# HP85disk.net
KiCad netlist of a schematic drawn in EAGLE
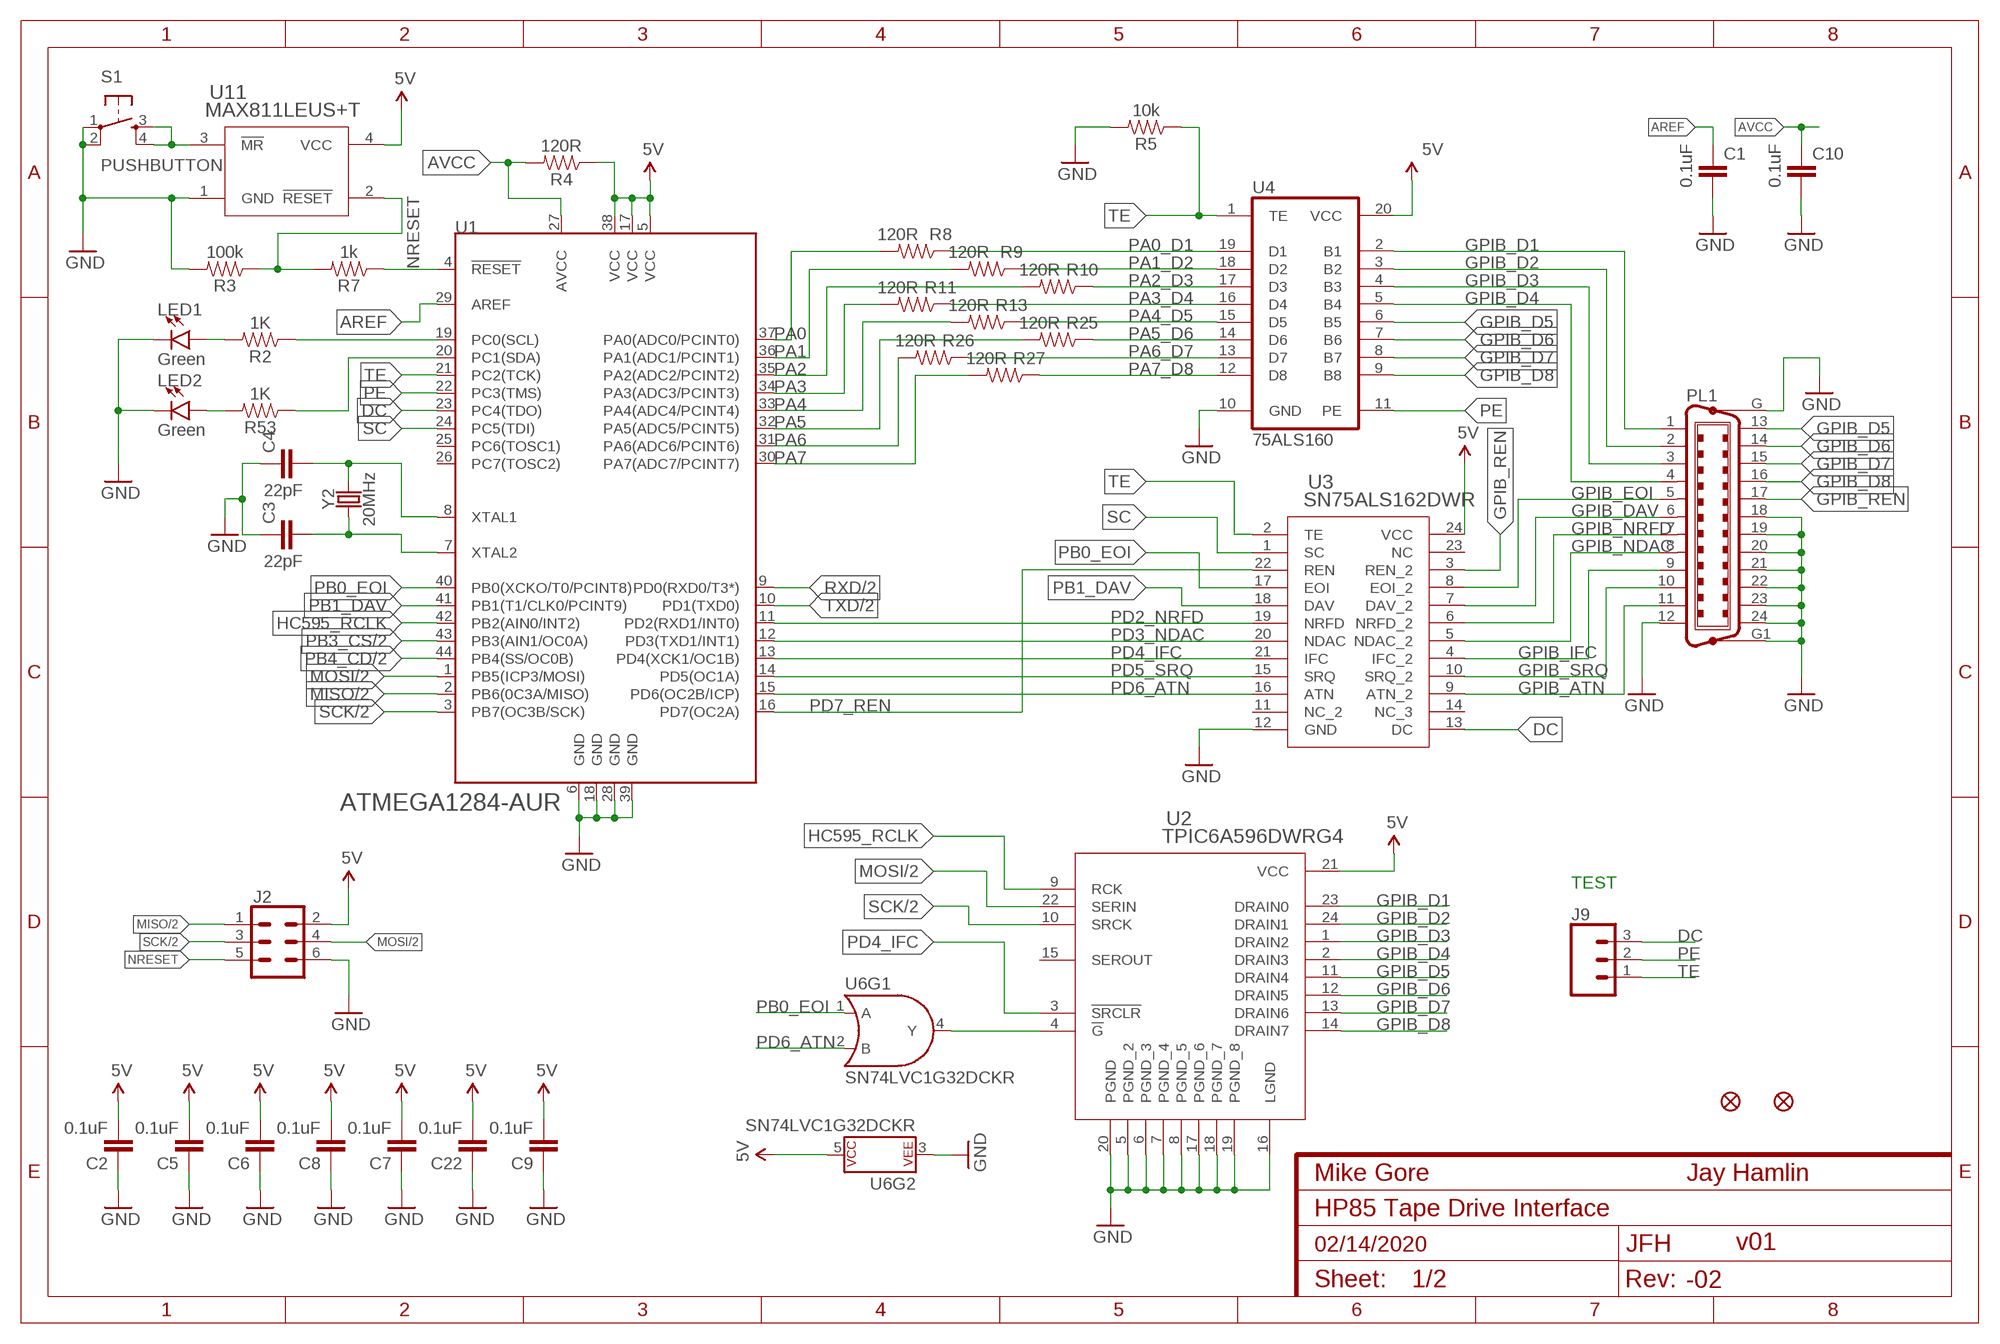
[diagram p0: schematic, sheet 1]
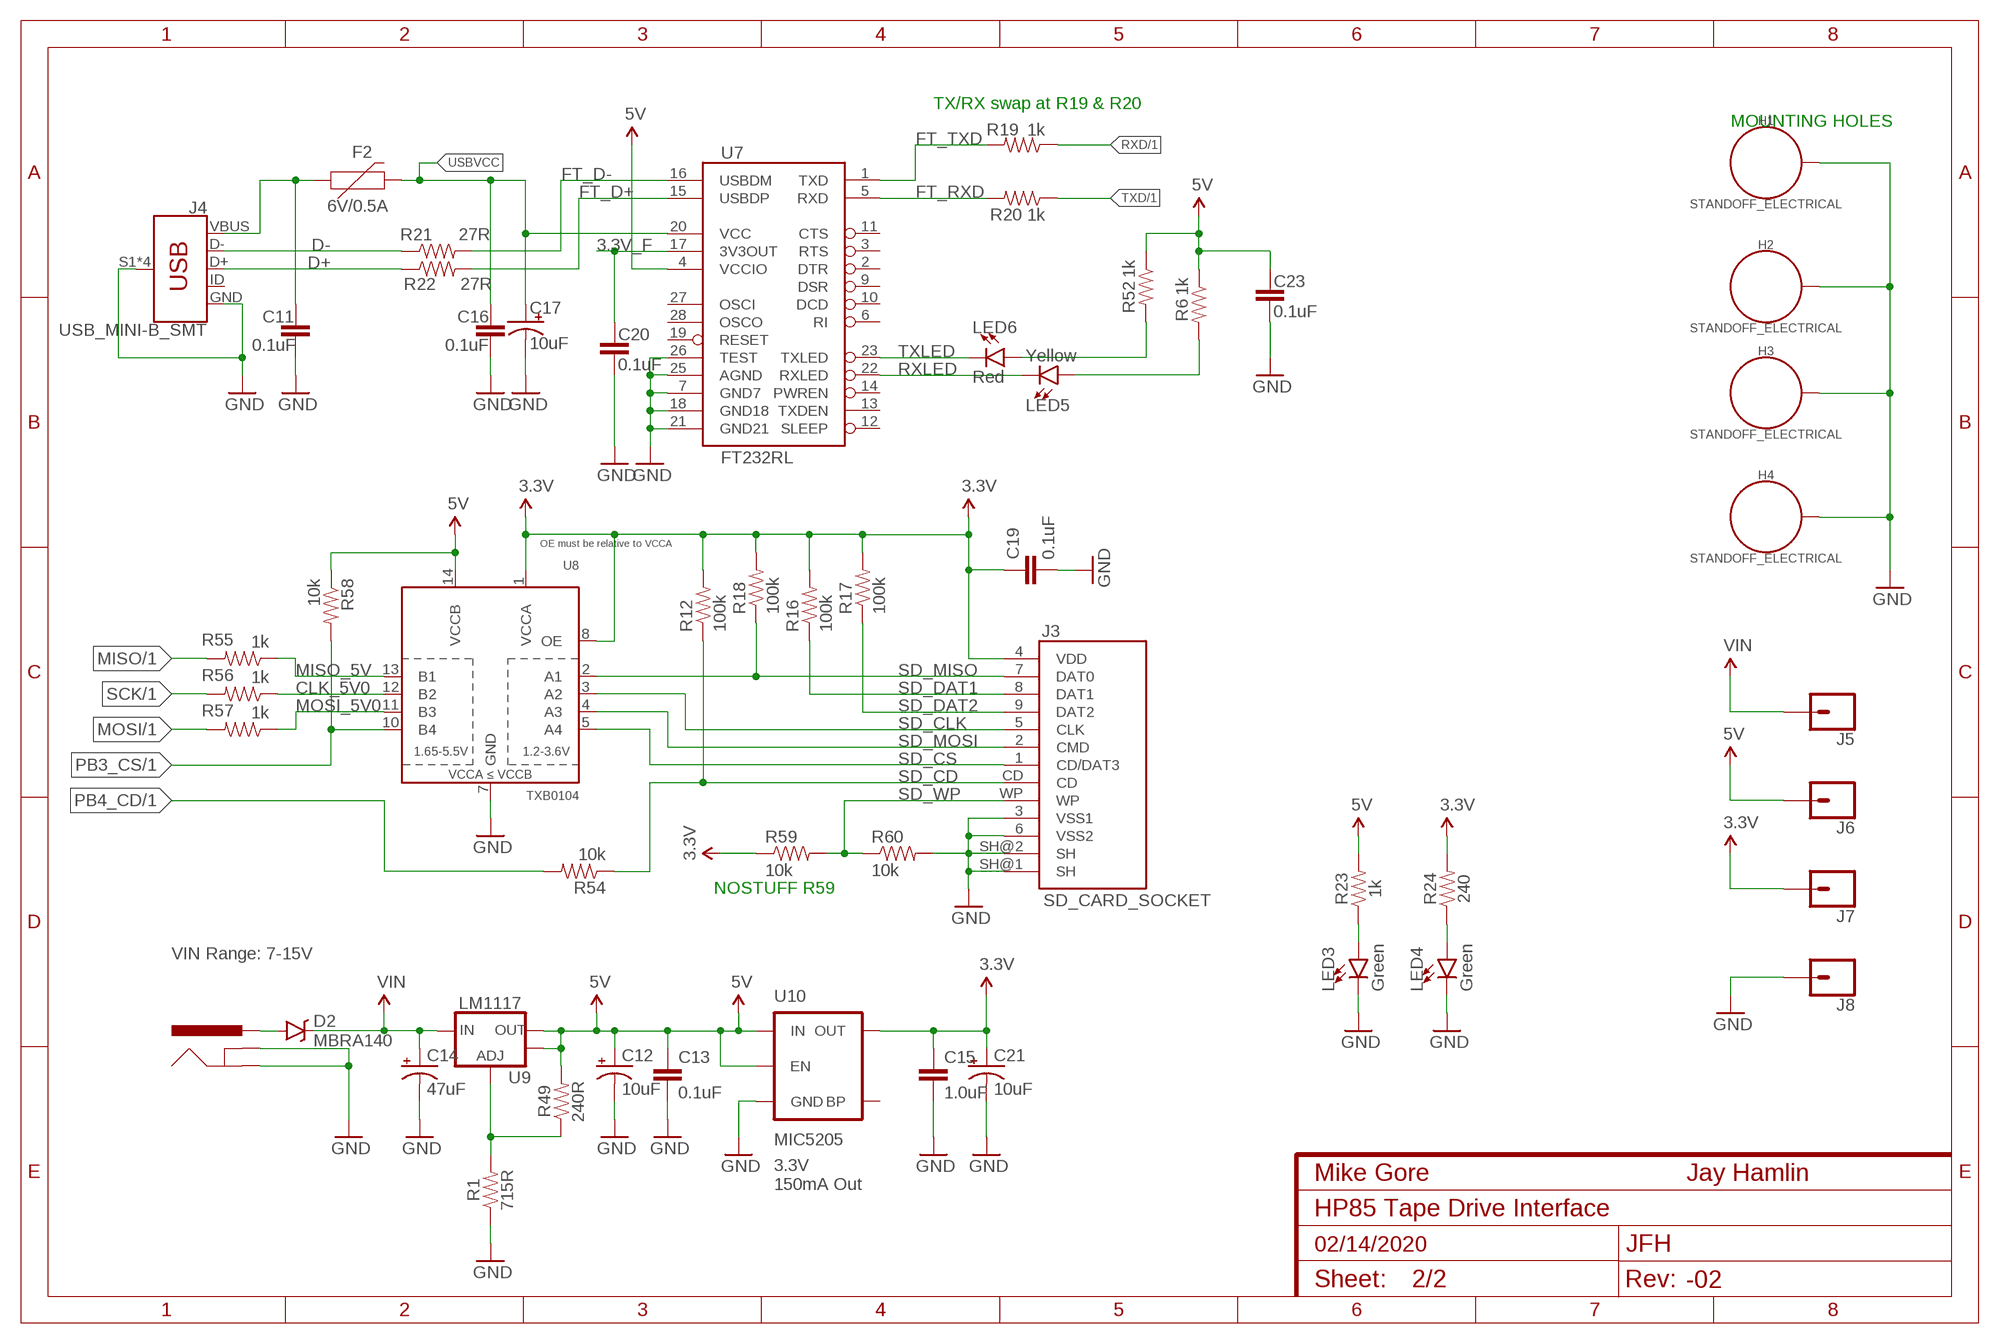
[diagram p1: schematic, sheet 2]

(export (version "E")
  (design (tool "Eeschema 10.0.6"))
  (components
    (comp (ref "C11")
      (value "0.1uF")
      (footprint "eagle-import:0603")
      (libsource (lib "eagle-import") (part "0.1UF-0603-25V-(+80/-20%)"))
    )
    (comp (ref "C12")
      (value "10uF")
      (footprint "eagle-import:EIA3216")
      (libsource (lib "eagle-import") (part "10UF-POLAR-EIA3216-16V-10%(TANT)"))
    )
    (comp (ref "C13")
      (value "0.1uF")
      (footprint "eagle-import:0603")
      (libsource (lib "eagle-import") (part "0.1UF-0603-25V-(+80/-20%)"))
    )
    (comp (ref "C14")
      (value "47uF")
      (footprint "eagle-import:PANASONIC_D")
      (libsource (lib "eagle-import") (part "47UF-POLAR-PANASONIC_D-35V-20%"))
    )
    (comp (ref "C15")
      (value "1.0uF")
      (footprint "eagle-import:0603")
      (libsource (lib "eagle-import") (part "1.0UF-0603-16V-10%"))
    )
    (comp (ref "C16")
      (value "0.1uF")
      (footprint "eagle-import:0603")
      (libsource (lib "eagle-import") (part "0.1UF-0603-25V-(+80/-20%)"))
    )
    (comp (ref "C17")
      (value "10uF")
      (footprint "eagle-import:EIA3216")
      (libsource (lib "eagle-import") (part "10UF-POLAR-EIA3216-16V-10%(TANT)"))
    )
    (comp (ref "C19")
      (value "0.1uF")
      (footprint "eagle-import:0603")
      (libsource (lib "eagle-import") (part "0.1UF-0603-25V-(+80/-20%)"))
    )
    (comp (ref "C20")
      (value "0.1uF")
      (footprint "eagle-import:0603")
      (libsource (lib "eagle-import") (part "0.1UF-0603-25V-(+80/-20%)"))
    )
    (comp (ref "C21")
      (value "10uF")
      (footprint "eagle-import:EIA3216")
      (libsource (lib "eagle-import") (part "10UF-POLAR-EIA3216-16V-10%(TANT)"))
    )
    (comp (ref "C23")
      (value "0.1uF")
      (footprint "eagle-import:0603")
      (libsource (lib "eagle-import") (part "0.1UF-0603-25V-(+80/-20%)"))
    )
    (comp (ref "D2")
      (value "MBRA140")
      (footprint "eagle-import:SMA-DIODE")
      (libsource (lib "eagle-import") (part "MBRA140"))
    )
    (comp (ref "F2")
      (value "6V/0.5A")
      (footprint "eagle-import:1206")
      (libsource (lib "eagle-import") (part "PTC-HALF_AMP"))
    )
    (comp (ref "H1")
      (value "STANDOFF_ELECTRICAL")
      (footprint "eagle-import:STANDOFF-ELECTRICAL")
      (libsource (lib "eagle-import") (part "STANDOFF_ELECTRICAL"))
    )
    (comp (ref "H2")
      (value "STANDOFF_ELECTRICAL")
      (footprint "eagle-import:STANDOFF-ELECTRICAL")
      (libsource (lib "eagle-import") (part "STANDOFF_ELECTRICAL"))
    )
    (comp (ref "H3")
      (value "STANDOFF_ELECTRICAL")
      (footprint "eagle-import:STANDOFF-ELECTRICAL")
      (libsource (lib "eagle-import") (part "STANDOFF_ELECTRICAL"))
    )
    (comp (ref "H4")
      (value "STANDOFF_ELECTRICAL")
      (footprint "eagle-import:STANDOFF-ELECTRICAL")
      (libsource (lib "eagle-import") (part "STANDOFF_ELECTRICAL"))
    )
    (comp (ref "J1")
      (value "POWER_JACKSUPER_BOMB_DIGITY")
      (footprint "eagle-import:POWER_JACK_SMD_OVERPASTE_SUPER_BOMB_DIGITY")
      (libsource (lib "eagle-import") (part "POWER_JACKSUPER_BOMB_DIGITY"))
    )
    (comp (ref "J3")
      (value "SD_CARD_SOCKET")
      (footprint "eagle-import:SD_1_1")
      (libsource (lib "eagle-import") (part "SD_CARD_SOCKET"))
    )
    (comp (ref "J4")
      (value "USB_MINI-B_SMT")
      (footprint "eagle-import:USB-MINIB")
      (libsource (lib "eagle-import") (part "USB_MINI-B_SMT"))
    )
    (comp (ref "J5")
      (value "CONN_01")
      (footprint "eagle-import:1X01")
      (libsource (lib "eagle-import") (part "CONN_01"))
    )
    (comp (ref "J6")
      (value "CONN_01")
      (footprint "eagle-import:1X01")
      (libsource (lib "eagle-import") (part "CONN_01"))
    )
    (comp (ref "J7")
      (value "CONN_01")
      (footprint "eagle-import:1X01")
      (libsource (lib "eagle-import") (part "CONN_01"))
    )
    (comp (ref "J8")
      (value "CONN_01")
      (footprint "eagle-import:1X01")
      (libsource (lib "eagle-import") (part "CONN_01"))
    )
    (comp (ref "LED3")
      (value "Green")
      (footprint "eagle-import:LED-1206")
      (libsource (lib "eagle-import") (part "LED1206"))
    )
    (comp (ref "LED4")
      (value "Green")
      (footprint "eagle-import:LED-1206")
      (libsource (lib "eagle-import") (part "LED1206"))
    )
    (comp (ref "LED5")
      (value "Yellow")
      (footprint "eagle-import:LED-1206")
      (libsource (lib "eagle-import") (part "LED1206"))
    )
    (comp (ref "LED6")
      (value "Red")
      (footprint "eagle-import:LED-1206")
      (libsource (lib "eagle-import") (part "LED1206"))
    )
    (comp (ref "R1")
      (value "715R")
      (footprint "eagle-import:0603")
      (libsource (lib "eagle-import") (part "715OHM-0603-1/10W-1%"))
    )
    (comp (ref "R6")
      (value "1k")
      (footprint "eagle-import:0603")
      (libsource (lib "eagle-import") (part "1KOHM-0603-1/10W-1%"))
    )
    (comp (ref "R12")
      (value "100k")
      (footprint "eagle-import:0603-RES")
      (libsource (lib "eagle-import") (part "100KOHM-1/10W-1%(0603)"))
    )
    (comp (ref "R16")
      (value "100k")
      (footprint "eagle-import:0603-RES")
      (libsource (lib "eagle-import") (part "100KOHM-1/10W-1%(0603)"))
    )
    (comp (ref "R17")
      (value "100k")
      (footprint "eagle-import:0603-RES")
      (libsource (lib "eagle-import") (part "100KOHM-1/10W-1%(0603)"))
    )
    (comp (ref "R18")
      (value "100k")
      (footprint "eagle-import:0603-RES")
      (libsource (lib "eagle-import") (part "100KOHM-1/10W-1%(0603)"))
    )
    (comp (ref "R19")
      (value "1k")
      (footprint "eagle-import:0603")
      (libsource (lib "eagle-import") (part "1KOHM-0603-1/10W-1%"))
    )
    (comp (ref "R20")
      (value "1k")
      (footprint "eagle-import:0603")
      (libsource (lib "eagle-import") (part "1KOHM-0603-1/10W-1%"))
    )
    (comp (ref "R21")
      (value "27R")
      (footprint "eagle-import:0603")
      (libsource (lib "eagle-import") (part "27OHM-0603-1/10W-1%"))
    )
    (comp (ref "R22")
      (value "27R")
      (footprint "eagle-import:0603")
      (libsource (lib "eagle-import") (part "27OHM-0603-1/10W-1%"))
    )
    (comp (ref "R23")
      (value "1k")
      (footprint "eagle-import:0603")
      (libsource (lib "eagle-import") (part "4.7KOHM-0603-1/10W-1%"))
    )
    (comp (ref "R24")
      (value "240")
      (footprint "eagle-import:0603")
      (libsource (lib "eagle-import") (part "4.7KOHM-0603-1/10W-1%"))
    )
    (comp (ref "R49")
      (value "240R")
      (footprint "eagle-import:0603")
      (libsource (lib "eagle-import") (part "240OHM-0603-1/10W-1%"))
    )
    (comp (ref "R52")
      (value "1k")
      (footprint "eagle-import:0603")
      (libsource (lib "eagle-import") (part "1KOHM-0603-1/10W-1%"))
    )
    (comp (ref "R54")
      (value "10k")
      (footprint "eagle-import:0603-RES")
      (libsource (lib "eagle-import") (part "100KOHM-1/10W-1%(0603)"))
    )
    (comp (ref "R55")
      (value "1k")
      (footprint "eagle-import:0603-RES")
      (libsource (lib "eagle-import") (part "100KOHM-1/10W-1%(0603)"))
    )
    (comp (ref "R56")
      (value "1k")
      (footprint "eagle-import:0603-RES")
      (libsource (lib "eagle-import") (part "100KOHM-1/10W-1%(0603)"))
    )
    (comp (ref "R57")
      (value "1k")
      (footprint "eagle-import:0603-RES")
      (libsource (lib "eagle-import") (part "100KOHM-1/10W-1%(0603)"))
    )
    (comp (ref "R58")
      (value "10k")
      (footprint "eagle-import:0603-RES")
      (libsource (lib "eagle-import") (part "100KOHM-1/10W-1%(0603)"))
    )
    (comp (ref "R59")
      (value "10k")
      (footprint "eagle-import:0603-RES")
      (libsource (lib "eagle-import") (part "100KOHM-1/10W-1%(0603)"))
    )
    (comp (ref "R60")
      (value "10k")
      (footprint "eagle-import:0603-RES")
      (libsource (lib "eagle-import") (part "100KOHM-1/10W-1%(0603)"))
    )
    (comp (ref "U7")
      (value "FT232RL")
      (footprint "eagle-import:SSOP28DB")
      (libsource (lib "eagle-import") (part "FT232RLSSOP"))
    )
    (comp (ref "U8")
      (value "TXB0104")
      (footprint "eagle-import:SO14")
      (libsource (lib "eagle-import") (part "TXB0104PWRSOIC14"))
    )
    (comp (ref "U9")
      (value "LM1117")
      (footprint "eagle-import:SOT223-ALT1")
      (libsource (lib "eagle-import") (part "V_REG_LM1117ALT1"))
    )
    (comp (ref "U10")
      (value "MIC5205")
      (footprint "eagle-import:SOT23-5")
      (libsource (lib "eagle-import") (part "MIC52053.3V"))
    )
    (comp (ref "C1")
      (value "0.1uF")
      (footprint "eagle-import:0603")
      (libsource (lib "eagle-import") (part "0.1UF-0603-25V-(+80/-20%)"))
    )
    (comp (ref "C2")
      (value "0.1uF")
      (footprint "eagle-import:0603")
      (fields (field (name "SPICEPREFIX") "C"))
      (libsource (lib "eagle-import") (part "0.1UF-0603-25V-(+80/-20%)"))
    )
    (comp (ref "C3")
      (value "22pF")
      (footprint "eagle-import:0603")
      (libsource (lib "eagle-import") (part "0.1UF-0603-25V-(+80/-20%)"))
    )
    (comp (ref "C4")
      (value "22pF")
      (footprint "eagle-import:0603")
      (libsource (lib "eagle-import") (part "0.1UF-0603-25V-(+80/-20%)"))
    )
    (comp (ref "C5")
      (value "0.1uF")
      (footprint "eagle-import:0603")
      (fields (field (name "SPICEPREFIX") "C"))
      (libsource (lib "eagle-import") (part "0.1UF-0603-25V-(+80/-20%)"))
    )
    (comp (ref "C6")
      (value "0.1uF")
      (footprint "eagle-import:0603")
      (fields (field (name "SPICEPREFIX") "C"))
      (libsource (lib "eagle-import") (part "0.1UF-0603-25V-(+80/-20%)"))
    )
    (comp (ref "C7")
      (value "0.1uF")
      (footprint "eagle-import:0603")
      (fields (field (name "SPICEPREFIX") "C"))
      (libsource (lib "eagle-import") (part "0.1UF-0603-25V-(+80/-20%)"))
    )
    (comp (ref "C8")
      (value "0.1uF")
      (footprint "eagle-import:0603")
      (fields (field (name "SPICEPREFIX") "C"))
      (libsource (lib "eagle-import") (part "0.1UF-0603-25V-(+80/-20%)"))
    )
    (comp (ref "C9")
      (value "0.1uF")
      (footprint "eagle-import:0603")
      (libsource (lib "eagle-import") (part "0.1UF-0603-25V-(+80/-20%)"))
    )
    (comp (ref "C10")
      (value "0.1uF")
      (footprint "eagle-import:0603")
      (libsource (lib "eagle-import") (part "0.1UF-0603-25V-(+80/-20%)"))
    )
    (comp (ref "C22")
      (value "0.1uF")
      (footprint "eagle-import:0603")
      (libsource (lib "eagle-import") (part "0.1UF-0603-25V-(+80/-20%)"))
    )
    (comp (ref "J2")
      (value "CONN_03X2_BIGPADSFEMALE_SMD")
      (footprint "eagle-import:2X3_SMD")
      (libsource (lib "eagle-import") (part "CONN_03X2_BIGPADSFEMALE_SMD"))
    )
    (comp (ref "J9")
      (value "CONN_03")
      (footprint "eagle-import:1X03")
      (libsource (lib "eagle-import") (part "CONN_03"))
    )
    (comp (ref "JP8")
      (value "FIDUCIAL1X2")
      (footprint "eagle-import:FIDUCIAL-1X2")
      (libsource (lib "eagle-import") (part "FIDUCIAL1X2"))
    )
    (comp (ref "JP9")
      (value "FIDUCIAL1X2")
      (footprint "eagle-import:FIDUCIAL-1X2")
      (libsource (lib "eagle-import") (part "FIDUCIAL1X2"))
    )
    (comp (ref "LED1")
      (value "Green")
      (footprint "eagle-import:LED-1206")
      (libsource (lib "eagle-import") (part "LED1206"))
    )
    (comp (ref "LED2")
      (value "Green")
      (footprint "eagle-import:LED-1206")
      (libsource (lib "eagle-import") (part "LED1206"))
    )
    (comp (ref "PL1")
      (value "C24HP")
      (footprint "eagle-import:24HP")
      (libsource (lib "eagle-import") (part "C24HP"))
    )
    (comp (ref "R2")
      (value "1K")
      (footprint "eagle-import:0603")
      (libsource (lib "eagle-import") (part "4.7KOHM-0603-1/10W-1%"))
    )
    (comp (ref "R3")
      (value "100k")
      (footprint "eagle-import:0603")
      (libsource (lib "eagle-import") (part "10KOHM-0603-1/10W-1%"))
    )
    (comp (ref "R4")
      (value "120R")
      (footprint "eagle-import:0603")
      (libsource (lib "eagle-import") (part "10KOHM-0603-1/10W-1%"))
    )
    (comp (ref "R5")
      (value "10k")
      (footprint "eagle-import:0603")
      (libsource (lib "eagle-import") (part "10KOHM-0603-1/10W-1%"))
    )
    (comp (ref "R7")
      (value "1k")
      (footprint "eagle-import:0603")
      (libsource (lib "eagle-import") (part "10KOHM-0603-1/10W-1%"))
    )
    (comp (ref "R8")
      (value "120R")
      (footprint "eagle-import:0603")
      (libsource (lib "eagle-import") (part "10KOHM-0603-1/10W-1%"))
    )
    (comp (ref "R9")
      (value "120R")
      (footprint "eagle-import:0603")
      (libsource (lib "eagle-import") (part "10KOHM-0603-1/10W-1%"))
    )
    (comp (ref "R10")
      (value "120R")
      (footprint "eagle-import:0603")
      (libsource (lib "eagle-import") (part "10KOHM-0603-1/10W-1%"))
    )
    (comp (ref "R11")
      (value "120R")
      (footprint "eagle-import:0603")
      (libsource (lib "eagle-import") (part "10KOHM-0603-1/10W-1%"))
    )
    (comp (ref "R13")
      (value "120R")
      (footprint "eagle-import:0603")
      (libsource (lib "eagle-import") (part "10KOHM-0603-1/10W-1%"))
    )
    (comp (ref "R25")
      (value "120R")
      (footprint "eagle-import:0603")
      (libsource (lib "eagle-import") (part "10KOHM-0603-1/10W-1%"))
    )
    (comp (ref "R26")
      (value "120R")
      (footprint "eagle-import:0603")
      (libsource (lib "eagle-import") (part "10KOHM-0603-1/10W-1%"))
    )
    (comp (ref "R27")
      (value "120R")
      (footprint "eagle-import:0603")
      (libsource (lib "eagle-import") (part "10KOHM-0603-1/10W-1%"))
    )
    (comp (ref "R53")
      (value "1K")
      (footprint "eagle-import:0603")
      (libsource (lib "eagle-import") (part "4.7KOHM-0603-1/10W-1%"))
    )
    (comp (ref "S1")
      (value "PUSHBUTTON")
      (footprint "eagle-import:TACTILE-SWITCH-SMD")
      (libsource (lib "eagle-import") (part "SWITCH_SPST_4_PINSQUARE"))
    )
    (comp (ref "U1")
      (value "ATMEGA1284-AUR")
      (footprint "eagle-import:TQFP44")
      (libsource (lib "eagle-import") (part "ATMEGA1284AUTQFP-44"))
    )
    (comp (ref "U2")
      (value "TPIC6A596DWRG4")
      (footprint "eagle-import:DW24")
      (fields (field (name "MANUFACTURER") "Texas Instruments"))
      (libsource (lib "eagle-import") (part "TPIC6A596DWRG4"))
    )
    (comp (ref "U3")
      (value "SN75ALS162DWR")
      (footprint "eagle-import:DW24")
      (fields (field (name "MANUFACTURER") "Texas Instruments"))
      (libsource (lib "eagle-import") (part "SN75ALS162DWR"))
    )
    (comp (ref "U4")
      (value "75ALS160")
      (footprint "eagle-import:SO20L")
      (libsource (lib "eagle-import") (part "75160SO"))
    )
    (comp (ref "U6")
      (value "SN74LVC1G32DCKR")
      (footprint "eagle-import:SOT23-5")
      (libsource (lib "eagle-import") (part "7432DBVLVC"))
    )
    (comp (ref "U11")
      (value "MAX811LEUS+T")
      (footprint "eagle-import:21-0052F")
      (fields
        (field (name "MANUFACTURER_PART_NUMBER") "MAX811TEUS+T")
        (field (name "COPYRIGHT") "Copyright (C) 2018 Accelerated Designs. All rights reserved")
      )
      (libsource (lib "eagle-import") (part "MAX811TEUS+T"))
    )
    (comp (ref "Y2")
      (value "20MHz")
      (footprint "eagle-import:CRYSTAL-SMD-5X3.2-4PAD")
      (libsource (lib "eagle-import") (part "CRYSTAL-16MHZSMD-5X3.2"))
    )
  )
  (nets
    (net (code "1") (name "3.3V") (class "Default")
      (node (ref "C15") (pin "1") (pinfunction "1_1") (pintype "passive"))
      (node (ref "C19") (pin "1") (pinfunction "1_1") (pintype "passive"))
      (node (ref "C21") (pin "+") (pinfunction "+_+") (pintype "passive"))
      (node (ref "J3") (pin "4") (pinfunction "VDD_4") (pintype "power_in"))
      (node (ref "J7") (pin "1") (pinfunction "1_1") (pintype "passive"))
      (node (ref "R12") (pin "2") (pinfunction "2_2") (pintype "passive"))
      (node (ref "R16") (pin "2") (pinfunction "2_2") (pintype "passive"))
      (node (ref "R17") (pin "2") (pinfunction "2_2") (pintype "passive"))
      (node (ref "R18") (pin "2") (pinfunction "2_2") (pintype "passive"))
      (node (ref "R24") (pin "2") (pinfunction "2_2") (pintype "passive"))
      (node (ref "R59") (pin "1") (pinfunction "1_1") (pintype "passive"))
      (node (ref "U10") (pin "5") (pinfunction "OUT_5") (pintype "passive"))
      (node (ref "U8") (pin "1") (pinfunction "VCCA_1") (pintype "bidirectional"))
      (node (ref "U8") (pin "8") (pinfunction "OE_8") (pintype "bidirectional"))
    )
    (net (code "2") (name "3.3V_F") (class "Default")
      (node (ref "C20") (pin "1") (pinfunction "1_1") (pintype "passive"))
      (node (ref "U7") (pin "17") (pinfunction "3V3OUT_17") (pintype "output"))
    )
    (net (code "3") (name "5V") (class "Default")
      (node (ref "C12") (pin "+") (pinfunction "+_+") (pintype "passive"))
      (node (ref "C13") (pin "1") (pinfunction "1_1") (pintype "passive"))
      (node (ref "C2") (pin "2") (pinfunction "2_2") (pintype "passive"))
      (node (ref "C22") (pin "2") (pinfunction "2_2") (pintype "passive"))
      (node (ref "C23") (pin "1") (pinfunction "1_1") (pintype "passive"))
      (node (ref "C5") (pin "2") (pinfunction "2_2") (pintype "passive"))
      (node (ref "C6") (pin "2") (pinfunction "2_2") (pintype "passive"))
      (node (ref "C7") (pin "2") (pinfunction "2_2") (pintype "passive"))
      (node (ref "C8") (pin "2") (pinfunction "2_2") (pintype "passive"))
      (node (ref "C9") (pin "2") (pinfunction "2_2") (pintype "passive"))
      (node (ref "J2") (pin "2") (pinfunction "2_2") (pintype "bidirectional"))
      (node (ref "J6") (pin "1") (pinfunction "1_1") (pintype "passive"))
      (node (ref "R23") (pin "2") (pinfunction "2_2") (pintype "passive"))
      (node (ref "R4") (pin "1") (pinfunction "1_1") (pintype "passive"))
      (node (ref "R49") (pin "2") (pinfunction "2_2") (pintype "passive"))
      (node (ref "R52") (pin "1") (pinfunction "1_1") (pintype "passive"))
      (node (ref "R58") (pin "1") (pinfunction "1_1") (pintype "passive"))
      (node (ref "R6") (pin "1") (pinfunction "1_1") (pintype "passive"))
      (node (ref "U1") (pin "17") (pinfunction "VCC_17") (pintype "bidirectional"))
      (node (ref "U1") (pin "38") (pinfunction "VCC_38") (pintype "bidirectional"))
      (node (ref "U1") (pin "5") (pinfunction "VCC_5") (pintype "bidirectional"))
      (node (ref "U10") (pin "1") (pinfunction "IN_1") (pintype "input"))
      (node (ref "U10") (pin "3") (pinfunction "EN_3") (pintype "input"))
      (node (ref "U11") (pin "4") (pinfunction "VCC_4") (pintype "power_in"))
      (node (ref "U2") (pin "21") (pinfunction "VCC_21") (pintype "power_in"))
      (node (ref "U3") (pin "24") (pinfunction "VCC_24") (pintype "power_in"))
      (node (ref "U4") (pin "20") (pinfunction "VCC_20") (pintype "bidirectional"))
      (node (ref "U6") (pin "5") (pinfunction "P$V+_5") (pintype "bidirectional"))
      (node (ref "U7") (pin "4") (pinfunction "VCCIO_4") (pintype "power_in"))
      (node (ref "U8") (pin "14") (pinfunction "VCCB_14") (pintype "bidirectional"))
      (node (ref "U9") (pin "2") (pinfunction "OUT_2") (pintype "output"))
      (node (ref "U9") (pin "4") (pinfunction "OUT_4") (pintype "output"))
    )
    (net (code "4") (name "AREF") (class "Default")
      (node (ref "C1") (pin "1") (pinfunction "1_1") (pintype "passive"))
      (node (ref "U1") (pin "29") (pinfunction "AREF_29") (pintype "bidirectional"))
    )
    (net (code "5") (name "AVCC") (class "Default")
      (node (ref "C10") (pin "1") (pinfunction "1_1") (pintype "passive"))
      (node (ref "R4") (pin "2") (pinfunction "2_2") (pintype "passive"))
      (node (ref "U1") (pin "27") (pinfunction "AVCC_27") (pintype "bidirectional"))
    )
    (net (code "6") (name "CLK_5V0") (class "Default")
      (node (ref "R56") (pin "1") (pinfunction "1_1") (pintype "passive"))
      (node (ref "U8") (pin "12") (pinfunction "B2_12") (pintype "bidirectional"))
    )
    (net (code "7") (name "D+") (class "Default")
      (node (ref "J4") (pin "D+") (pinfunction "D+_D+") (pintype "bidirectional"))
      (node (ref "R22") (pin "1") (pinfunction "1_1") (pintype "passive"))
    )
    (net (code "8") (name "D-") (class "Default")
      (node (ref "J4") (pin "D-") (pinfunction "D-_D-") (pintype "bidirectional"))
      (node (ref "R21") (pin "1") (pinfunction "1_1") (pintype "passive"))
    )
    (net (code "9") (name "DC") (class "Default")
      (node (ref "J9") (pin "3") (pinfunction "3_3") (pintype "passive"))
      (node (ref "U1") (pin "23") (pinfunction "PC4(TDO)_23") (pintype "bidirectional"))
      (node (ref "U3") (pin "13") (pinfunction "DC_13") (pintype "input"))
    )
    (net (code "10") (name "FT_D+") (class "Default")
      (node (ref "R22") (pin "2") (pinfunction "2_2") (pintype "passive"))
      (node (ref "U7") (pin "15") (pinfunction "USBDP_15") (pintype "bidirectional"))
    )
    (net (code "11") (name "FT_D-") (class "Default")
      (node (ref "R21") (pin "2") (pinfunction "2_2") (pintype "passive"))
      (node (ref "U7") (pin "16") (pinfunction "USBDM_16") (pintype "bidirectional"))
    )
    (net (code "12") (name "FT_RXD") (class "Default")
      (node (ref "R20") (pin "2") (pinfunction "2_2") (pintype "passive"))
      (node (ref "U7") (pin "5") (pinfunction "RXD_5") (pintype "input"))
    )
    (net (code "13") (name "FT_TXD") (class "Default")
      (node (ref "R19") (pin "2") (pinfunction "2_2") (pintype "passive"))
      (node (ref "U7") (pin "1") (pinfunction "TXD_1") (pintype "output"))
    )
    (net (code "14") (name "GND") (class "Default")
      (node (ref "C1") (pin "2") (pinfunction "2_2") (pintype "passive"))
      (node (ref "C10") (pin "2") (pinfunction "2_2") (pintype "passive"))
      (node (ref "C11") (pin "2") (pinfunction "2_2") (pintype "passive"))
      (node (ref "C12") (pin "-") (pinfunction "-_-") (pintype "passive"))
      (node (ref "C13") (pin "2") (pinfunction "2_2") (pintype "passive"))
      (node (ref "C14") (pin "-") (pinfunction "-_-") (pintype "passive"))
      (node (ref "C15") (pin "2") (pinfunction "2_2") (pintype "passive"))
      (node (ref "C16") (pin "2") (pinfunction "2_2") (pintype "passive"))
      (node (ref "C17") (pin "-") (pinfunction "-_-") (pintype "passive"))
      (node (ref "C19") (pin "2") (pinfunction "2_2") (pintype "passive"))
      (node (ref "C2") (pin "1") (pinfunction "1_1") (pintype "passive"))
      (node (ref "C20") (pin "2") (pinfunction "2_2") (pintype "passive"))
      (node (ref "C21") (pin "-") (pinfunction "-_-") (pintype "passive"))
      (node (ref "C22") (pin "1") (pinfunction "1_1") (pintype "passive"))
      (node (ref "C23") (pin "2") (pinfunction "2_2") (pintype "passive"))
      (node (ref "C3") (pin "1") (pinfunction "1_1") (pintype "passive"))
      (node (ref "C4") (pin "1") (pinfunction "1_1") (pintype "passive"))
      (node (ref "C5") (pin "1") (pinfunction "1_1") (pintype "passive"))
      (node (ref "C6") (pin "1") (pinfunction "1_1") (pintype "passive"))
      (node (ref "C7") (pin "1") (pinfunction "1_1") (pintype "passive"))
      (node (ref "C8") (pin "1") (pinfunction "1_1") (pintype "passive"))
      (node (ref "C9") (pin "1") (pinfunction "1_1") (pintype "passive"))
      (node (ref "H1") (pin "P1") (pinfunction "P$1_P1") (pintype "bidirectional"))
      (node (ref "H2") (pin "P1") (pinfunction "P$1_P1") (pintype "bidirectional"))
      (node (ref "H3") (pin "P1") (pinfunction "P$1_P1") (pintype "bidirectional"))
      (node (ref "H4") (pin "P1") (pinfunction "P$1_P1") (pintype "bidirectional"))
      (node (ref "J1") (pin "GND") (pinfunction "GNDBREAK_GND") (pintype "bidirectional"))
      (node (ref "J1") (pin "P$4") (pinfunction "GND_P$4") (pintype "bidirectional"))
      (node (ref "J2") (pin "6") (pinfunction "6_6") (pintype "bidirectional"))
      (node (ref "J3") (pin "3") (pinfunction "VSS1_3") (pintype "power_in"))
      (node (ref "J3") (pin "6") (pinfunction "VSS2_6") (pintype "power_in"))
      (node (ref "J3") (pin "SH@1") (pinfunction "SH_SH@1") (pintype "bidirectional"))
      (node (ref "J3") (pin "SH@2") (pinfunction "SH_SH@2") (pintype "bidirectional"))
      (node (ref "J4") (pin "GND") (pinfunction "GND_GND") (pintype "power_in"))
      (node (ref "J4") (pin "S1") (pinfunction "SHIELD_S1") (pintype "bidirectional"))
      (node (ref "J4") (pin "S2") (pinfunction "SHIELD_S2") (pintype "bidirectional"))
      (node (ref "J4") (pin "S3") (pinfunction "SHIELD_S3") (pintype "bidirectional"))
      (node (ref "J4") (pin "S4") (pinfunction "SHIELD_S4") (pintype "bidirectional"))
      (node (ref "J8") (pin "1") (pinfunction "1_1") (pintype "passive"))
      (node (ref "LED1") (pin "C") (pinfunction "C_C") (pintype "passive"))
      (node (ref "LED2") (pin "C") (pinfunction "C_C") (pintype "passive"))
      (node (ref "LED3") (pin "C") (pinfunction "C_C") (pintype "passive"))
      (node (ref "LED4") (pin "C") (pinfunction "C_C") (pintype "passive"))
      (node (ref "PL1") (pin "12") (pinfunction "12_12") (pintype "passive"))
      (node (ref "PL1") (pin "18") (pinfunction "18_18") (pintype "passive"))
      (node (ref "PL1") (pin "19") (pinfunction "19_19") (pintype "passive"))
      (node (ref "PL1") (pin "20") (pinfunction "20_20") (pintype "passive"))
      (node (ref "PL1") (pin "21") (pinfunction "21_21") (pintype "passive"))
      (node (ref "PL1") (pin "22") (pinfunction "22_22") (pintype "passive"))
      (node (ref "PL1") (pin "23") (pinfunction "23_23") (pintype "passive"))
      (node (ref "PL1") (pin "24") (pinfunction "24_24") (pintype "passive"))
      (node (ref "PL1") (pin "G") (pinfunction "G_G") (pintype "passive"))
      (node (ref "PL1") (pin "G1") (pinfunction "G1_G1") (pintype "passive"))
      (node (ref "R1") (pin "1") (pinfunction "1_1") (pintype "passive"))
      (node (ref "R3") (pin "2") (pinfunction "2_2") (pintype "passive"))
      (node (ref "R5") (pin "2") (pinfunction "2_2") (pintype "passive"))
      (node (ref "R60") (pin "2") (pinfunction "2_2") (pintype "passive"))
      (node (ref "S1") (pin "1") (pinfunction "1_1") (pintype "passive"))
      (node (ref "S1") (pin "2") (pinfunction "2_2") (pintype "passive"))
      (node (ref "U1") (pin "18") (pinfunction "GND_18") (pintype "bidirectional"))
      (node (ref "U1") (pin "28") (pinfunction "GND_28") (pintype "bidirectional"))
      (node (ref "U1") (pin "39") (pinfunction "GND_39") (pintype "bidirectional"))
      (node (ref "U1") (pin "6") (pinfunction "GND_6") (pintype "bidirectional"))
      (node (ref "U10") (pin "2") (pinfunction "GND_2") (pintype "input"))
      (node (ref "U11") (pin "1") (pinfunction "GND_1") (pintype "power_in"))
      (node (ref "U2") (pin "16") (pinfunction "LGND_16") (pintype "power_in"))
      (node (ref "U2") (pin "17") (pinfunction "PGND_6_17") (pintype "power_in"))
      (node (ref "U2") (pin "18") (pinfunction "PGND_7_18") (pintype "power_in"))
      (node (ref "U2") (pin "19") (pinfunction "PGND_8_19") (pintype "power_in"))
      (node (ref "U2") (pin "20") (pinfunction "PGND_20") (pintype "power_in"))
      (node (ref "U2") (pin "5") (pinfunction "PGND_2_5") (pintype "power_in"))
      (node (ref "U2") (pin "6") (pinfunction "PGND_3_6") (pintype "power_in"))
      (node (ref "U2") (pin "7") (pinfunction "PGND_4_7") (pintype "power_in"))
      (node (ref "U2") (pin "8") (pinfunction "PGND_5_8") (pintype "power_in"))
      (node (ref "U3") (pin "12") (pinfunction "GND_12") (pintype "power_in"))
      (node (ref "U4") (pin "10") (pinfunction "GND_10") (pintype "bidirectional"))
      (node (ref "U6") (pin "3") (pinfunction "P$V-_3") (pintype "bidirectional"))
      (node (ref "U7") (pin "18") (pinfunction "GND18_18") (pintype "power_in"))
      (node (ref "U7") (pin "21") (pinfunction "GND21_21") (pintype "power_in"))
      (node (ref "U7") (pin "25") (pinfunction "AGND_25") (pintype "power_in"))
      (node (ref "U7") (pin "26") (pinfunction "TEST_26") (pintype "input"))
      (node (ref "U7") (pin "7") (pinfunction "GND7_7") (pintype "power_in"))
      (node (ref "U8") (pin "7") (pinfunction "GND_7") (pintype "bidirectional"))
    )
    (net (code "15") (name "GPIB_ATN") (class "Default")
      (node (ref "PL1") (pin "11") (pinfunction "11_11") (pintype "passive"))
      (node (ref "U3") (pin "9") (pinfunction "ATN_2_9") (pintype "bidirectional"))
    )
    (net (code "16") (name "GPIB_D1") (class "Default")
      (node (ref "PL1") (pin "1") (pinfunction "1_1") (pintype "passive"))
      (node (ref "U2") (pin "23") (pinfunction "DRAIN0_23") (pintype "output"))
      (node (ref "U4") (pin "2") (pinfunction "B1_2") (pintype "bidirectional"))
    )
    (net (code "17") (name "GPIB_D2") (class "Default")
      (node (ref "PL1") (pin "2") (pinfunction "2_2") (pintype "passive"))
      (node (ref "U2") (pin "24") (pinfunction "DRAIN1_24") (pintype "output"))
      (node (ref "U4") (pin "3") (pinfunction "B2_3") (pintype "bidirectional"))
    )
    (net (code "18") (name "GPIB_D3") (class "Default")
      (node (ref "PL1") (pin "3") (pinfunction "3_3") (pintype "passive"))
      (node (ref "U2") (pin "1") (pinfunction "DRAIN2_1") (pintype "output"))
      (node (ref "U4") (pin "4") (pinfunction "B3_4") (pintype "bidirectional"))
    )
    (net (code "19") (name "GPIB_D4") (class "Default")
      (node (ref "PL1") (pin "4") (pinfunction "4_4") (pintype "passive"))
      (node (ref "U2") (pin "2") (pinfunction "DRAIN3_2") (pintype "output"))
      (node (ref "U4") (pin "5") (pinfunction "B4_5") (pintype "bidirectional"))
    )
    (net (code "20") (name "GPIB_D5") (class "Default")
      (node (ref "PL1") (pin "13") (pinfunction "13_13") (pintype "passive"))
      (node (ref "U2") (pin "11") (pinfunction "DRAIN4_11") (pintype "output"))
      (node (ref "U4") (pin "6") (pinfunction "B5_6") (pintype "bidirectional"))
    )
    (net (code "21") (name "GPIB_D6") (class "Default")
      (node (ref "PL1") (pin "14") (pinfunction "14_14") (pintype "passive"))
      (node (ref "U2") (pin "12") (pinfunction "DRAIN5_12") (pintype "output"))
      (node (ref "U4") (pin "7") (pinfunction "B6_7") (pintype "bidirectional"))
    )
    (net (code "22") (name "GPIB_D7") (class "Default")
      (node (ref "PL1") (pin "15") (pinfunction "15_15") (pintype "passive"))
      (node (ref "U2") (pin "13") (pinfunction "DRAIN6_13") (pintype "output"))
      (node (ref "U4") (pin "8") (pinfunction "B7_8") (pintype "bidirectional"))
    )
    (net (code "23") (name "GPIB_D8") (class "Default")
      (node (ref "PL1") (pin "16") (pinfunction "16_16") (pintype "passive"))
      (node (ref "U2") (pin "14") (pinfunction "DRAIN7_14") (pintype "output"))
      (node (ref "U4") (pin "9") (pinfunction "B8_9") (pintype "bidirectional"))
    )
    (net (code "24") (name "GPIB_DAV") (class "Default")
      (node (ref "PL1") (pin "6") (pinfunction "6_6") (pintype "passive"))
      (node (ref "U3") (pin "7") (pinfunction "DAV_2_7") (pintype "bidirectional"))
    )
    (net (code "25") (name "GPIB_EOI") (class "Default")
      (node (ref "PL1") (pin "5") (pinfunction "5_5") (pintype "passive"))
      (node (ref "U3") (pin "8") (pinfunction "EOI_2_8") (pintype "bidirectional"))
    )
    (net (code "26") (name "GPIB_IFC") (class "Default")
      (node (ref "PL1") (pin "9") (pinfunction "9_9") (pintype "passive"))
      (node (ref "U3") (pin "4") (pinfunction "IFC_2_4") (pintype "bidirectional"))
    )
    (net (code "27") (name "GPIB_NDAC") (class "Default")
      (node (ref "PL1") (pin "8") (pinfunction "8_8") (pintype "passive"))
      (node (ref "U3") (pin "5") (pinfunction "NDAC_2_5") (pintype "bidirectional"))
    )
    (net (code "28") (name "GPIB_NRFD") (class "Default")
      (node (ref "PL1") (pin "7") (pinfunction "7_7") (pintype "passive"))
      (node (ref "U3") (pin "6") (pinfunction "NRFD_2_6") (pintype "bidirectional"))
    )
    (net (code "29") (name "GPIB_REN") (class "Default")
      (node (ref "PL1") (pin "17") (pinfunction "17_17") (pintype "passive"))
      (node (ref "U3") (pin "3") (pinfunction "REN_2_3") (pintype "bidirectional"))
    )
    (net (code "30") (name "GPIB_SRQ") (class "Default")
      (node (ref "PL1") (pin "10") (pinfunction "10_10") (pintype "passive"))
      (node (ref "U3") (pin "10") (pinfunction "SRQ_2_10") (pintype "bidirectional"))
    )
    (net (code "31") (name "HC595_RCLK") (class "Default")
      (node (ref "U1") (pin "42") (pinfunction "PB2(AIN0/INT2)_42") (pintype "bidirectional"))
      (node (ref "U2") (pin "9") (pinfunction "RCK_9") (pintype "input"))
    )
    (net (code "32") (name "MISO") (class "Default")
      (node (ref "J2") (pin "1") (pinfunction "1_1") (pintype "bidirectional"))
      (node (ref "R55") (pin "2") (pinfunction "2_2") (pintype "passive"))
      (node (ref "U1") (pin "2") (pinfunction "PB6(0C3A/MISO)_2") (pintype "bidirectional"))
    )
    (net (code "33") (name "MISO_5V") (class "Default")
      (node (ref "R55") (pin "1") (pinfunction "1_1") (pintype "passive"))
      (node (ref "U8") (pin "13") (pinfunction "B1_13") (pintype "bidirectional"))
    )
    (net (code "34") (name "MOSI") (class "Default")
      (node (ref "J2") (pin "4") (pinfunction "4_4") (pintype "bidirectional"))
      (node (ref "R57") (pin "2") (pinfunction "2_2") (pintype "passive"))
      (node (ref "U1") (pin "1") (pinfunction "PB5(ICP3/MOSI)_1") (pintype "bidirectional"))
      (node (ref "U2") (pin "22") (pinfunction "SERIN_22") (pintype "input"))
    )
    (net (code "35") (name "MOSI_5V0") (class "Default")
      (node (ref "R57") (pin "1") (pinfunction "1_1") (pintype "passive"))
      (node (ref "U8") (pin "11") (pinfunction "B3_11") (pintype "bidirectional"))
    )
    (net (code "36") (name "NRESET") (class "Default")
      (node (ref "J2") (pin "5") (pinfunction "5_5") (pintype "bidirectional"))
      (node (ref "R7") (pin "1") (pinfunction "1_1") (pintype "passive"))
      (node (ref "U1") (pin "4") (pinfunction "~{RESET}_4") (pintype "bidirectional"))
    )
    (net (code "37") (name "Net-(C11-Pad1)") (class "Default")
      (node (ref "C11") (pin "1") (pinfunction "1_1") (pintype "passive"))
      (node (ref "F2") (pin "1") (pinfunction "1_1") (pintype "bidirectional"))
      (node (ref "J4") (pin "VBUS") (pinfunction "VBUS_VBUS") (pintype "power_in"))
    )
    (net (code "38") (name "Net-(J1-PWR)") (class "Default")
      (node (ref "D2") (pin "A") (pinfunction "A_A") (pintype "passive"))
      (node (ref "J1") (pin "VIN0") (pinfunction "PWR_VIN0") (pintype "bidirectional"))
    )
    (net (code "39") (name "Net-(LED1-PadA)") (class "Default")
      (node (ref "LED1") (pin "A") (pinfunction "A_A") (pintype "passive"))
      (node (ref "R2") (pin "2") (pinfunction "2_2") (pintype "passive"))
    )
    (net (code "40") (name "Net-(LED2-PadA)") (class "Default")
      (node (ref "LED2") (pin "A") (pinfunction "A_A") (pintype "passive"))
      (node (ref "R53") (pin "2") (pinfunction "2_2") (pintype "passive"))
    )
    (net (code "41") (name "Net-(LED3-PadA)") (class "Default")
      (node (ref "LED3") (pin "A") (pinfunction "A_A") (pintype "passive"))
      (node (ref "R23") (pin "1") (pinfunction "1_1") (pintype "passive"))
    )
    (net (code "42") (name "Net-(LED4-PadA)") (class "Default")
      (node (ref "LED4") (pin "A") (pinfunction "A_A") (pintype "passive"))
      (node (ref "R24") (pin "1") (pinfunction "1_1") (pintype "passive"))
    )
    (net (code "43") (name "Net-(LED5-PadA)") (class "Default")
      (node (ref "LED5") (pin "A") (pinfunction "A_A") (pintype "passive"))
      (node (ref "R6") (pin "2") (pinfunction "2_2") (pintype "passive"))
    )
    (net (code "44") (name "Net-(LED6-PadA)") (class "Default")
      (node (ref "LED6") (pin "A") (pinfunction "A_A") (pintype "passive"))
      (node (ref "R52") (pin "2") (pinfunction "2_2") (pintype "passive"))
    )
    (net (code "45") (name "Net-(U1-PC0(SCL))") (class "Default")
      (node (ref "R2") (pin "1") (pinfunction "1_1") (pintype "passive"))
      (node (ref "U1") (pin "19") (pinfunction "PC0(SCL)_19") (pintype "bidirectional"))
    )
    (net (code "46") (name "Net-(U1-PC1(SDA))") (class "Default")
      (node (ref "R53") (pin "1") (pinfunction "1_1") (pintype "passive"))
      (node (ref "U1") (pin "20") (pinfunction "PC1(SDA)_20") (pintype "bidirectional"))
    )
    (net (code "47") (name "Net-(U1-XTAL1)") (class "Default")
      (node (ref "C4") (pin "2") (pinfunction "2_2") (pintype "passive"))
      (node (ref "U1") (pin "8") (pinfunction "XTAL1_8") (pintype "bidirectional"))
      (node (ref "Y2") (pin "3") (pinfunction "2_3") (pintype "passive"))
    )
    (net (code "48") (name "Net-(U1-XTAL2)") (class "Default")
      (node (ref "C3") (pin "2") (pinfunction "2_2") (pintype "passive"))
      (node (ref "U1") (pin "7") (pinfunction "XTAL2_7") (pintype "bidirectional"))
      (node (ref "Y2") (pin "1") (pinfunction "1_1") (pintype "passive"))
    )
    (net (code "49") (name "Net-(U2-~{G})") (class "Default")
      (node (ref "U2") (pin "4") (pinfunction "~{G}_4") (pintype "input"))
      (node (ref "U6") (pin "4") (pinfunction "Y_4") (pintype "bidirectional"))
    )
    (net (code "50") (name "Net-(U9-ADJ)") (class "Default")
      (node (ref "R1") (pin "2") (pinfunction "2_2") (pintype "passive"))
      (node (ref "R49") (pin "1") (pinfunction "1_1") (pintype "passive"))
      (node (ref "U9") (pin "1") (pinfunction "ADJ_1") (pintype "input"))
    )
    (net (code "51") (name "Net-(U11-~{MR})") (class "Default")
      (node (ref "S1") (pin "3") (pinfunction "3_3") (pintype "passive"))
      (node (ref "S1") (pin "4") (pinfunction "4_4") (pintype "passive"))
      (node (ref "U11") (pin "3") (pinfunction "~{MR}_3") (pintype "input"))
    )
    (net (code "52") (name "Net-(U11-~{RESET})") (class "Default")
      (node (ref "R3") (pin "1") (pinfunction "1_1") (pintype "passive"))
      (node (ref "R7") (pin "2") (pinfunction "2_2") (pintype "passive"))
      (node (ref "U11") (pin "2") (pinfunction "~{RESET}_2") (pintype "output"))
    )
    (net (code "53") (name "PA0") (class "Default")
      (node (ref "R8") (pin "2") (pinfunction "2_2") (pintype "passive"))
      (node (ref "U1") (pin "37") (pinfunction "PA0(ADC0/PCINT0)_37") (pintype "bidirectional"))
    )
    (net (code "54") (name "PA0_D1") (class "Default")
      (node (ref "R8") (pin "1") (pinfunction "1_1") (pintype "passive"))
      (node (ref "U4") (pin "19") (pinfunction "D1_19") (pintype "bidirectional"))
    )
    (net (code "55") (name "PA1") (class "Default")
      (node (ref "R9") (pin "2") (pinfunction "2_2") (pintype "passive"))
      (node (ref "U1") (pin "36") (pinfunction "PA1(ADC1/PCINT1)_36") (pintype "bidirectional"))
    )
    (net (code "56") (name "PA1_D2") (class "Default")
      (node (ref "R9") (pin "1") (pinfunction "1_1") (pintype "passive"))
      (node (ref "U4") (pin "18") (pinfunction "D2_18") (pintype "bidirectional"))
    )
    (net (code "57") (name "PA2") (class "Default")
      (node (ref "R10") (pin "2") (pinfunction "2_2") (pintype "passive"))
      (node (ref "U1") (pin "35") (pinfunction "PA2(ADC2/PCINT2)_35") (pintype "bidirectional"))
    )
    (net (code "58") (name "PA2_D3") (class "Default")
      (node (ref "R10") (pin "1") (pinfunction "1_1") (pintype "passive"))
      (node (ref "U4") (pin "17") (pinfunction "D3_17") (pintype "bidirectional"))
    )
    (net (code "59") (name "PA3") (class "Default")
      (node (ref "R11") (pin "2") (pinfunction "2_2") (pintype "passive"))
      (node (ref "U1") (pin "34") (pinfunction "PA3(ADC3/PCINT3)_34") (pintype "bidirectional"))
    )
    (net (code "60") (name "PA3_D4") (class "Default")
      (node (ref "R11") (pin "1") (pinfunction "1_1") (pintype "passive"))
      (node (ref "U4") (pin "16") (pinfunction "D4_16") (pintype "bidirectional"))
    )
    (net (code "61") (name "PA4") (class "Default")
      (node (ref "R13") (pin "2") (pinfunction "2_2") (pintype "passive"))
      (node (ref "U1") (pin "33") (pinfunction "PA4(ADC4/PCINT4)_33") (pintype "bidirectional"))
    )
    (net (code "62") (name "PA4_D5") (class "Default")
      (node (ref "R13") (pin "1") (pinfunction "1_1") (pintype "passive"))
      (node (ref "U4") (pin "15") (pinfunction "D5_15") (pintype "bidirectional"))
    )
    (net (code "63") (name "PA5") (class "Default")
      (node (ref "R25") (pin "2") (pinfunction "2_2") (pintype "passive"))
      (node (ref "U1") (pin "32") (pinfunction "PA5(ADC5/PCINT5)_32") (pintype "bidirectional"))
    )
    (net (code "64") (name "PA5_D6") (class "Default")
      (node (ref "R25") (pin "1") (pinfunction "1_1") (pintype "passive"))
      (node (ref "U4") (pin "14") (pinfunction "D6_14") (pintype "bidirectional"))
    )
    (net (code "65") (name "PA6") (class "Default")
      (node (ref "R26") (pin "2") (pinfunction "2_2") (pintype "passive"))
      (node (ref "U1") (pin "31") (pinfunction "PA6(ADC6/PCINT6)_31") (pintype "bidirectional"))
    )
    (net (code "66") (name "PA6_D7") (class "Default")
      (node (ref "R26") (pin "1") (pinfunction "1_1") (pintype "passive"))
      (node (ref "U4") (pin "13") (pinfunction "D7_13") (pintype "bidirectional"))
    )
    (net (code "67") (name "PA7") (class "Default")
      (node (ref "R27") (pin "2") (pinfunction "2_2") (pintype "passive"))
      (node (ref "U1") (pin "30") (pinfunction "PA7(ADC7/PCINT7)_30") (pintype "bidirectional"))
    )
    (net (code "68") (name "PA7_D8") (class "Default")
      (node (ref "R27") (pin "1") (pinfunction "1_1") (pintype "passive"))
      (node (ref "U4") (pin "12") (pinfunction "D8_12") (pintype "bidirectional"))
    )
    (net (code "69") (name "PB0_EOI") (class "Default")
      (node (ref "U1") (pin "40") (pinfunction "PB0(XCKO/T0/PCINT8)_40") (pintype "bidirectional"))
      (node (ref "U3") (pin "17") (pinfunction "EOI_17") (pintype "bidirectional"))
      (node (ref "U6") (pin "1") (pinfunction "A_1") (pintype "bidirectional"))
    )
    (net (code "70") (name "PB1_DAV") (class "Default")
      (node (ref "U1") (pin "41") (pinfunction "PB1(T1/CLK0/PCINT9)_41") (pintype "bidirectional"))
      (node (ref "U3") (pin "18") (pinfunction "DAV_18") (pintype "bidirectional"))
    )
    (net (code "71") (name "PB3_CS") (class "Default")
      (node (ref "R58") (pin "2") (pinfunction "2_2") (pintype "passive"))
      (node (ref "U1") (pin "43") (pinfunction "PB3(AIN1/OC0A)_43") (pintype "bidirectional"))
      (node (ref "U8") (pin "10") (pinfunction "B4_10") (pintype "bidirectional"))
    )
    (net (code "72") (name "PB4_CD") (class "Default")
      (node (ref "R54") (pin "2") (pinfunction "2_2") (pintype "passive"))
      (node (ref "U1") (pin "44") (pinfunction "PB4(SS/OC0B)_44") (pintype "bidirectional"))
    )
    (net (code "73") (name "PD2_NRFD") (class "Default")
      (node (ref "U1") (pin "11") (pinfunction "PD2(RXD1/INT0)_11") (pintype "bidirectional"))
      (node (ref "U3") (pin "19") (pinfunction "NRFD_19") (pintype "bidirectional"))
    )
    (net (code "74") (name "PD3_NDAC") (class "Default")
      (node (ref "U1") (pin "12") (pinfunction "PD3(TXD1/INT1)_12") (pintype "bidirectional"))
      (node (ref "U3") (pin "20") (pinfunction "NDAC_20") (pintype "bidirectional"))
    )
    (net (code "75") (name "PD4_IFC") (class "Default")
      (node (ref "U1") (pin "13") (pinfunction "PD4(XCK1/OC1B)_13") (pintype "bidirectional"))
      (node (ref "U2") (pin "3") (pinfunction "~{SRCLR}_3") (pintype "input"))
      (node (ref "U3") (pin "21") (pinfunction "IFC_21") (pintype "bidirectional"))
    )
    (net (code "76") (name "PD5_SRQ") (class "Default")
      (node (ref "U1") (pin "14") (pinfunction "PD5(OC1A)_14") (pintype "bidirectional"))
      (node (ref "U3") (pin "15") (pinfunction "SRQ_15") (pintype "bidirectional"))
    )
    (net (code "77") (name "PD6_ATN") (class "Default")
      (node (ref "U1") (pin "15") (pinfunction "PD6(OC2B/ICP)_15") (pintype "bidirectional"))
      (node (ref "U3") (pin "16") (pinfunction "ATN_16") (pintype "bidirectional"))
      (node (ref "U6") (pin "2") (pinfunction "B_2") (pintype "bidirectional"))
    )
    (net (code "78") (name "PD7_REN") (class "Default")
      (node (ref "U1") (pin "16") (pinfunction "PD7(OC2A)_16") (pintype "bidirectional"))
      (node (ref "U3") (pin "22") (pinfunction "REN_22") (pintype "bidirectional"))
    )
    (net (code "79") (name "PE") (class "Default")
      (node (ref "J9") (pin "2") (pinfunction "2_2") (pintype "passive"))
      (node (ref "U1") (pin "22") (pinfunction "PC3(TMS)_22") (pintype "bidirectional"))
      (node (ref "U4") (pin "11") (pinfunction "PE_11") (pintype "input"))
    )
    (net (code "80") (name "RXD") (class "Default")
      (node (ref "R19") (pin "1") (pinfunction "1_1") (pintype "passive"))
      (node (ref "U1") (pin "9") (pinfunction "PD0(RXD0/T3*)_9") (pintype "bidirectional"))
    )
    (net (code "81") (name "RXLED") (class "Default")
      (node (ref "LED5") (pin "C") (pinfunction "C_C") (pintype "passive"))
      (node (ref "U7") (pin "22") (pinfunction "RXLED_22") (pintype "input"))
    )
    (net (code "82") (name "SC") (class "Default")
      (node (ref "U1") (pin "24") (pinfunction "PC5(TDI)_24") (pintype "bidirectional"))
      (node (ref "U3") (pin "1") (pinfunction "SC_1") (pintype "input"))
    )
    (net (code "83") (name "SCK") (class "Default")
      (node (ref "J2") (pin "3") (pinfunction "3_3") (pintype "bidirectional"))
      (node (ref "R56") (pin "2") (pinfunction "2_2") (pintype "passive"))
      (node (ref "U1") (pin "3") (pinfunction "PB7(OC3B/SCK)_3") (pintype "bidirectional"))
      (node (ref "U2") (pin "10") (pinfunction "SRCK_10") (pintype "input"))
    )
    (net (code "84") (name "SD_CD") (class "Default")
      (node (ref "J3") (pin "CD") (pinfunction "CD_CD") (pintype "bidirectional"))
      (node (ref "R12") (pin "1") (pinfunction "1_1") (pintype "passive"))
      (node (ref "R54") (pin "1") (pinfunction "1_1") (pintype "passive"))
    )
    (net (code "85") (name "SD_CLK") (class "Default")
      (node (ref "J3") (pin "5") (pinfunction "CLK_5") (pintype "bidirectional"))
      (node (ref "U8") (pin "3") (pinfunction "A2_3") (pintype "bidirectional"))
    )
    (net (code "86") (name "SD_CS") (class "Default")
      (node (ref "J3") (pin "1") (pinfunction "CD/DAT3_1") (pintype "bidirectional"))
      (node (ref "U8") (pin "5") (pinfunction "A4_5") (pintype "bidirectional"))
    )
    (net (code "87") (name "SD_DAT1") (class "Default")
      (node (ref "J3") (pin "8") (pinfunction "DAT1_8") (pintype "bidirectional"))
      (node (ref "R16") (pin "1") (pinfunction "1_1") (pintype "passive"))
    )
    (net (code "88") (name "SD_DAT2") (class "Default")
      (node (ref "J3") (pin "9") (pinfunction "DAT2_9") (pintype "bidirectional"))
      (node (ref "R17") (pin "1") (pinfunction "1_1") (pintype "passive"))
    )
    (net (code "89") (name "SD_MISO") (class "Default")
      (node (ref "J3") (pin "7") (pinfunction "DAT0_7") (pintype "bidirectional"))
      (node (ref "R18") (pin "1") (pinfunction "1_1") (pintype "passive"))
      (node (ref "U8") (pin "2") (pinfunction "A1_2") (pintype "bidirectional"))
    )
    (net (code "90") (name "SD_MOSI") (class "Default")
      (node (ref "J3") (pin "2") (pinfunction "CMD_2") (pintype "bidirectional"))
      (node (ref "U8") (pin "4") (pinfunction "A3_4") (pintype "bidirectional"))
    )
    (net (code "91") (name "SD_WP") (class "Default")
      (node (ref "J3") (pin "WP") (pinfunction "WP_WP") (pintype "bidirectional"))
      (node (ref "R59") (pin "2") (pinfunction "2_2") (pintype "passive"))
      (node (ref "R60") (pin "1") (pinfunction "1_1") (pintype "passive"))
    )
    (net (code "92") (name "TE") (class "Default")
      (node (ref "J9") (pin "1") (pinfunction "1_1") (pintype "passive"))
      (node (ref "R5") (pin "1") (pinfunction "1_1") (pintype "passive"))
      (node (ref "U1") (pin "21") (pinfunction "PC2(TCK)_21") (pintype "bidirectional"))
      (node (ref "U3") (pin "2") (pinfunction "TE_2") (pintype "input"))
      (node (ref "U4") (pin "1") (pinfunction "TE_1") (pintype "input"))
    )
    (net (code "93") (name "TXD") (class "Default")
      (node (ref "R20") (pin "1") (pinfunction "1_1") (pintype "passive"))
      (node (ref "U1") (pin "10") (pinfunction "PD1(TXD0)_10") (pintype "bidirectional"))
    )
    (net (code "94") (name "TXLED") (class "Default")
      (node (ref "LED6") (pin "C") (pinfunction "C_C") (pintype "passive"))
      (node (ref "U7") (pin "23") (pinfunction "TXLED_23") (pintype "input"))
    )
    (net (code "95") (name "USBVCC") (class "Default")
      (node (ref "C16") (pin "1") (pinfunction "1_1") (pintype "passive"))
      (node (ref "C17") (pin "+") (pinfunction "+_+") (pintype "passive"))
      (node (ref "F2") (pin "2") (pinfunction "2_2") (pintype "bidirectional"))
      (node (ref "U7") (pin "20") (pinfunction "VCC_20") (pintype "power_in"))
    )
    (net (code "96") (name "VIN") (class "Default")
      (node (ref "C14") (pin "+") (pinfunction "+_+") (pintype "passive"))
      (node (ref "D2") (pin "C") (pinfunction "C_C") (pintype "passive"))
      (node (ref "J5") (pin "1") (pinfunction "1_1") (pintype "passive"))
      (node (ref "U9") (pin "3") (pinfunction "IN_3") (pintype "input"))
    )
    (net (code "97") (name "unconnected-(J4-PadID)") (class "Default")
      (node (ref "J4") (pin "ID") (pinfunction "ID_ID") (pintype "bidirectional"))
    )
    (net (code "98") (name "unconnected-(U1-PC6(TOSC1)-Pad25)") (class "Default")
      (node (ref "U1") (pin "25") (pinfunction "PC6(TOSC1)_25") (pintype "bidirectional"))
    )
    (net (code "99") (name "unconnected-(U1-PC7(TOSC2)-Pad26)") (class "Default")
      (node (ref "U1") (pin "26") (pinfunction "PC7(TOSC2)_26") (pintype "bidirectional"))
    )
    (net (code "100") (name "unconnected-(U2-SEROUT-Pad15)") (class "Default")
      (node (ref "U2") (pin "15") (pinfunction "SEROUT_15") (pintype "output"))
    )
    (net (code "101") (name "unconnected-(U3-NC-Pad23)") (class "Default")
      (node (ref "U3") (pin "23") (pinfunction "NC_23") (pintype "passive"))
    )
    (net (code "102") (name "unconnected-(U3-NC_2-Pad11)") (class "Default")
      (node (ref "U3") (pin "11") (pinfunction "NC_2_11") (pintype "passive"))
    )
    (net (code "103") (name "unconnected-(U3-NC_3-Pad14)") (class "Default")
      (node (ref "U3") (pin "14") (pinfunction "NC_3_14") (pintype "passive"))
    )
    (net (code "104") (name "unconnected-(U7-CTS-Pad11)") (class "Default")
      (node (ref "U7") (pin "11") (pinfunction "CTS_11") (pintype "input"))
    )
    (net (code "105") (name "unconnected-(U7-DCD-Pad10)") (class "Default")
      (node (ref "U7") (pin "10") (pinfunction "DCD_10") (pintype "input"))
    )
    (net (code "106") (name "unconnected-(U7-DSR-Pad9)") (class "Default")
      (node (ref "U7") (pin "9") (pinfunction "DSR_9") (pintype "input"))
    )
    (net (code "107") (name "unconnected-(U7-DTR-Pad2)") (class "Default")
      (node (ref "U7") (pin "2") (pinfunction "DTR_2") (pintype "output"))
    )
    (net (code "108") (name "unconnected-(U7-OSCI-Pad27)") (class "Default")
      (node (ref "U7") (pin "27") (pinfunction "OSCI_27") (pintype "input"))
    )
    (net (code "109") (name "unconnected-(U7-OSCO-Pad28)") (class "Default")
      (node (ref "U7") (pin "28") (pinfunction "OSCO_28") (pintype "output"))
    )
    (net (code "110") (name "unconnected-(U7-PWREN-Pad14)") (class "Default")
      (node (ref "U7") (pin "14") (pinfunction "PWREN_14") (pintype "input"))
    )
    (net (code "111") (name "unconnected-(U7-RESET-Pad19)") (class "Default")
      (node (ref "U7") (pin "19") (pinfunction "RESET_19") (pintype "input"))
    )
    (net (code "112") (name "unconnected-(U7-RI-Pad6)") (class "Default")
      (node (ref "U7") (pin "6") (pinfunction "RI_6") (pintype "input"))
    )
    (net (code "113") (name "unconnected-(U7-RTS-Pad3)") (class "Default")
      (node (ref "U7") (pin "3") (pinfunction "RTS_3") (pintype "output"))
    )
    (net (code "114") (name "unconnected-(U7-SLEEP-Pad12)") (class "Default")
      (node (ref "U7") (pin "12") (pinfunction "SLEEP_12") (pintype "input"))
    )
    (net (code "115") (name "unconnected-(U7-TXDEN-Pad13)") (class "Default")
      (node (ref "U7") (pin "13") (pinfunction "TXDEN_13") (pintype "input"))
    )
    (net (code "116") (name "unconnected-(U10-BP-Pad4)") (class "Default")
      (node (ref "U10") (pin "4") (pinfunction "BP_4") (pintype "input"))
    )
  )
)
